# power.net
KiCad netlist of a schematic drawn in Altium Designer
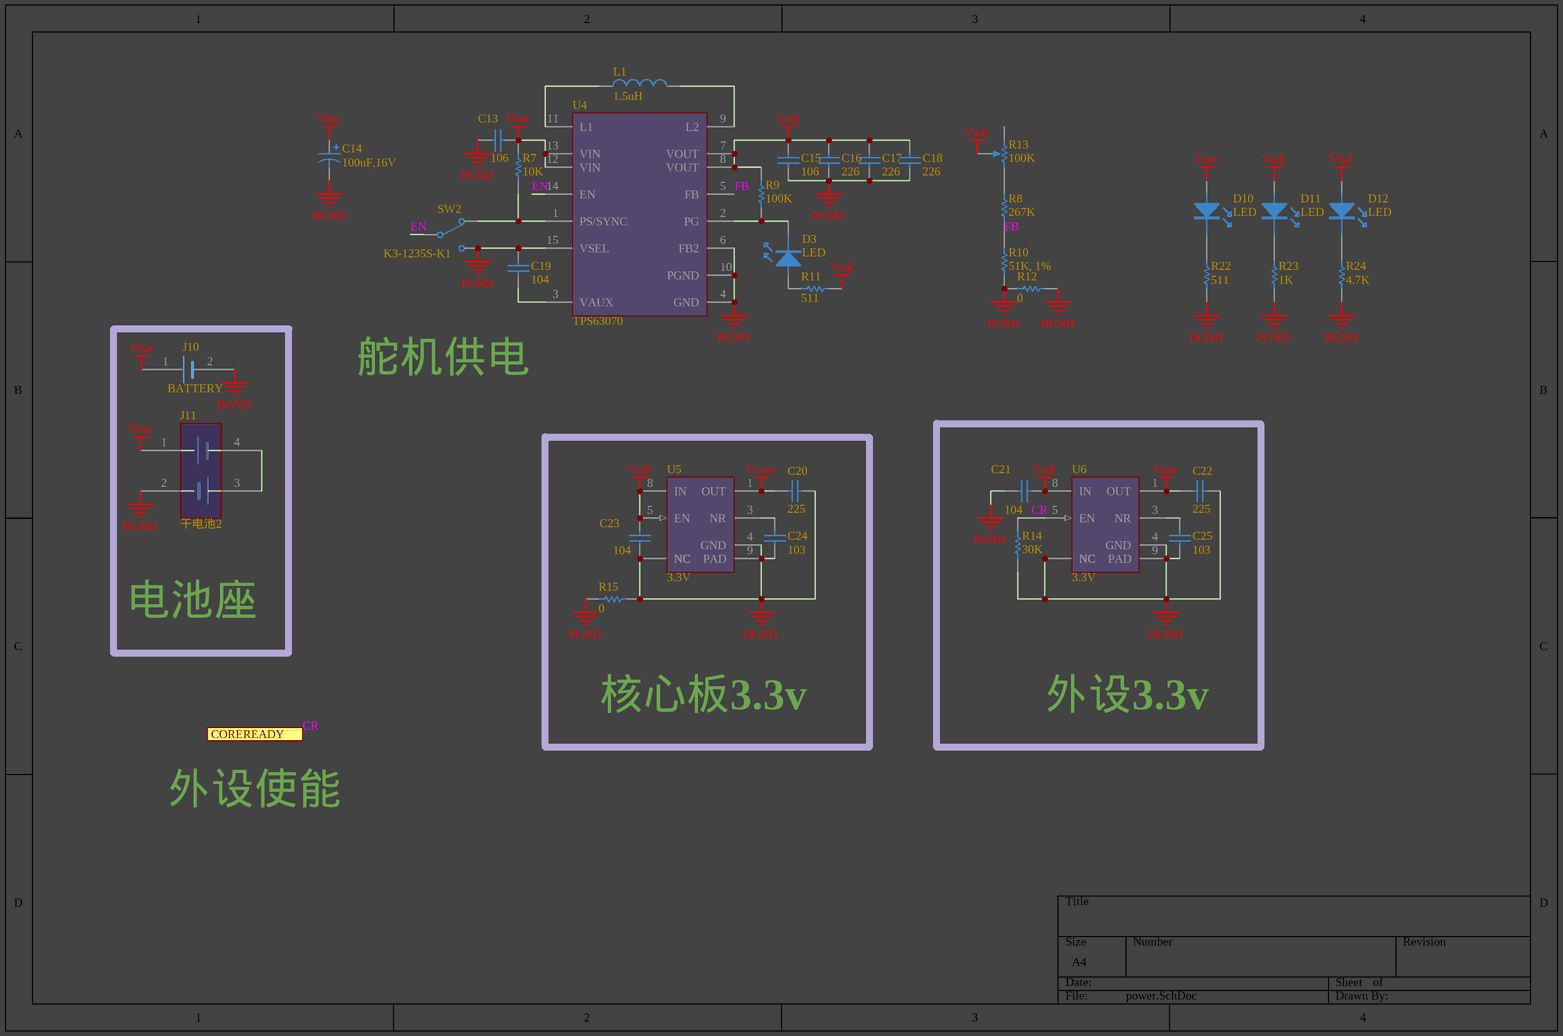
[diagram p0: power.SchDoc]

(export (version "E")
  (design (tool "Eeschema 10.0.6"))
  (components
    (comp (ref "C13")
      (value "106")
      (footprint "C0603")
      (description "Capacitor")
      (fields (field (name "PUBLISHER") "Altium Limited"))
      (libsource (lib "iMag") (part "电容"))
    )
    (comp (ref "C14")
      (value "100uF,16V")
      (footprint "贴片电解 6.3*5.4")
      (description "Polarized Capacitor (Axial)")
      (fields (field (name "PUBLISHER") "Altium Limited"))
      (libsource (lib "iMag") (part "电解电容"))
    )
    (comp (ref "C15")
      (value "106")
      (footprint "C0603")
      (description "Capacitor")
      (fields (field (name "PUBLISHER") "Altium Limited"))
      (libsource (lib "iMag") (part "电容"))
    )
    (comp (ref "C16")
      (value "226")
      (footprint "0805C")
      (description "Capacitor")
      (fields (field (name "PUBLISHER") "Altium Limited"))
      (libsource (lib "iMag") (part "电容"))
    )
    (comp (ref "C17")
      (value "226")
      (footprint "0805C")
      (description "Capacitor")
      (fields (field (name "PUBLISHER") "Altium Limited"))
      (libsource (lib "iMag") (part "电容"))
    )
    (comp (ref "C18")
      (value "226")
      (footprint "0805C")
      (description "Capacitor")
      (fields (field (name "PUBLISHER") "Altium Limited"))
      (libsource (lib "iMag") (part "电容"))
    )
    (comp (ref "C19")
      (value "104")
      (footprint "C0402")
      (description "Capacitor")
      (fields (field (name "PUBLISHER") "Altium Limited"))
      (libsource (lib "iMag") (part "电容"))
    )
    (comp (ref "C20")
      (value "225")
      (footprint "C0603")
      (description "X5R Capacitor")
      (fields (field (name "PUBLISHER") "Altium Limited"))
      (libsource (lib "iMag") (part "电容"))
    )
    (comp (ref "C21")
      (value "104")
      (footprint "C0402")
      (description "Capacitor")
      (fields (field (name "PUBLISHER") "Altium Limited"))
      (libsource (lib "iMag") (part "电容"))
    )
    (comp (ref "C22")
      (value "225")
      (footprint "C0603")
      (description "X5R Capacitor")
      (fields (field (name "PUBLISHER") "Altium Limited"))
      (libsource (lib "iMag") (part "电容"))
    )
    (comp (ref "C23")
      (value "104")
      (footprint "C0402")
      (description "Capacitor")
      (fields (field (name "PUBLISHER") "Altium Limited"))
      (libsource (lib "iMag") (part "电容"))
    )
    (comp (ref "C24")
      (value "103")
      (footprint "C0402")
      (description "Capacitor")
      (fields (field (name "PUBLISHER") "Altium Limited"))
      (libsource (lib "iMag") (part "电容"))
    )
    (comp (ref "C25")
      (value "103")
      (footprint "C0402")
      (description "Capacitor")
      (fields (field (name "PUBLISHER") "Altium Limited"))
      (libsource (lib "iMag") (part "电容"))
    )
    (comp (ref "D3") (value "LED") (footprint "LED 0603R") (libsource (lib "iMag") (part "LED")))
    (comp (ref "D10") (value "LED") (footprint "LED 0603Y") (libsource (lib "iMag") (part "LED")))
    (comp (ref "D11") (value "LED") (footprint "LED 0603G") (libsource (lib "iMag") (part "LED")))
    (comp (ref "D12") (value "LED") (footprint "LED 0603B") (libsource (lib "iMag") (part "LED")))
    (comp (ref "J10") (value "BATTERY") (footprint "T接头") (libsource (lib "iMag") (part "BATTERY")))
    (comp (ref "J11") (value "干电池2") (footprint "18650x2") (libsource (lib "iMag") (part "干电池2")))
    (comp (ref "L1")
      (value "1.5uH")
      (footprint "L5X5")
      (description "4.6A, 14.4mOhm")
      (libsource (lib "iMag") (part "贴片电感"))
    )
    (comp (ref "R7")
      (value "10K")
      (footprint "R0402")
      (description "Resistor")
      (fields (field (name "PUBLISHER") "Altium Limited"))
      (libsource (lib "iMag") (part "电阻"))
    )
    (comp (ref "R8")
      (value "267K")
      (footprint "R0402")
      (description "Resistor")
      (fields (field (name "PUBLISHER") "Altium Limited"))
      (libsource (lib "iMag") (part "电阻"))
    )
    (comp (ref "R9")
      (value "100K")
      (footprint "R0402")
      (description "Resistor")
      (fields (field (name "PUBLISHER") "Altium Limited"))
      (libsource (lib "iMag") (part "电阻"))
    )
    (comp (ref "R10")
      (value "51K, 1%")
      (footprint "R0402")
      (description "Resistor")
      (fields (field (name "PUBLISHER") "Altium Limited"))
      (libsource (lib "iMag") (part "电阻"))
    )
    (comp (ref "R11")
      (value "511")
      (footprint "R0402")
      (description "Resistor")
      (fields (field (name "PUBLISHER") "Altium Limited"))
      (libsource (lib "iMag") (part "电阻"))
    )
    (comp (ref "R12")
      (value "0")
      (footprint "R0603")
      (description "Resistor")
      (fields (field (name "PUBLISHER") "Altium Limited"))
      (libsource (lib "iMag") (part "电阻"))
    )
    (comp (ref "R13") (value "100K") (footprint "3296W") (libsource (lib "iMag") (part "电位器")))
    (comp (ref "R14")
      (value "30K")
      (footprint "R0402")
      (description "Resistor")
      (fields (field (name "PUBLISHER") "Altium Limited"))
      (libsource (lib "iMag") (part "电阻"))
    )
    (comp (ref "R15")
      (value "0")
      (footprint "R0603")
      (description "Resistor")
      (fields (field (name "PUBLISHER") "Altium Limited"))
      (libsource (lib "iMag") (part "电阻"))
    )
    (comp (ref "R22")
      (value "511")
      (footprint "R0402")
      (description "Resistor")
      (fields (field (name "PUBLISHER") "Altium Limited"))
      (libsource (lib "iMag") (part "电阻"))
    )
    (comp (ref "R23")
      (value "1K")
      (footprint "R0402")
      (description "Resistor")
      (fields (field (name "PUBLISHER") "Altium Limited"))
      (libsource (lib "iMag") (part "电阻"))
    )
    (comp (ref "R24")
      (value "4.7K")
      (footprint "R0402")
      (description "Resistor")
      (fields (field (name "PUBLISHER") "Altium Limited"))
      (libsource (lib "iMag") (part "电阻"))
    )
    (comp (ref "SW2")
      (value "K3-1235S-K1")
      (footprint "K3-1235S-K1")
      (description "Switch")
      (libsource (lib "iMag") (part "单刀双掷"))
    )
    (comp (ref "U4") (value "TPS63070") (footprint "VQFN-15") (libsource (lib "iMag") (part "TPS63070")))
    (comp (ref "U5")
      (value "3.3V")
      (footprint "VSON-8")
      (description "No Description Available")
      (fields
        (field (name "PARTNUMBER") "TPS73512DRBR")
        (field (name "ALTERNATE_PARTNUMBER") "TPS73512DRBT")
        (field (name "COPYRIGHT") "Copyright (C) 2018 Accelerated Designs. All rights reserved")
      )
      (libsource (lib "iMag") (part "TPS73512DRBR"))
    )
    (comp (ref "U6")
      (value "3.3V")
      (footprint "VSON-8")
      (description "No Description Available")
      (fields
        (field (name "PARTNUMBER") "TPS73512DRBR")
        (field (name "ALTERNATE_PARTNUMBER") "TPS73512DRBT")
        (field (name "COPYRIGHT") "Copyright (C) 2018 Accelerated Designs. All rights reserved")
      )
      (libsource (lib "iMag") (part "TPS73512DRBR"))
    )
  )
  (nets
    (net (code "1") (name "/CR") (class "Default")
      (node (ref "R14") (pin "1") (pinfunction "1_1") (pintype "passive"))
      (node (ref "U6") (pin "5") (pinfunction "EN_5") (pintype "input"))
    )
    (net (code "2") (name "/EN") (class "Default")
      (node (ref "SW2") (pin "2") (pinfunction "2_2") (pintype "passive"))
      (node (ref "U4") (pin "14") (pinfunction "EN_14") (pintype "passive"))
    )
    (net (code "3") (name "/FB") (class "Default")
      (node (ref "R10") (pin "1") (pinfunction "1_1") (pintype "passive"))
      (node (ref "R8") (pin "2") (pinfunction "2_2") (pintype "passive"))
      (node (ref "U4") (pin "5") (pinfunction "FB_5") (pintype "passive"))
    )
    (net (code "4") (name "BGND") (class "Default")
      (node (ref "C14") (pin "2") (pinfunction "2_2") (pintype "passive"))
      (node (ref "J10") (pin "2") (pinfunction "+_2") (pintype "passive"))
      (node (ref "J11") (pin "2") (pinfunction "+_2") (pintype "passive"))
      (node (ref "R12") (pin "1") (pinfunction "1_1") (pintype "passive"))
      (node (ref "R24") (pin "1") (pinfunction "1_1") (pintype "passive"))
    )
    (net (code "5") (name "DGND") (class "Default")
      (node (ref "C20") (pin "2") (pinfunction "2_2") (pintype "passive"))
      (node (ref "C22") (pin "2") (pinfunction "2_2") (pintype "passive"))
      (node (ref "C23") (pin "1") (pinfunction "1_1") (pintype "passive"))
      (node (ref "C24") (pin "1") (pinfunction "1_1") (pintype "passive"))
      (node (ref "C25") (pin "1") (pinfunction "1_1") (pintype "passive"))
      (node (ref "R14") (pin "2") (pinfunction "2_2") (pintype "passive"))
      (node (ref "R15") (pin "1") (pinfunction "1_1") (pintype "passive"))
      (node (ref "R22") (pin "1") (pinfunction "1_1") (pintype "passive"))
      (node (ref "U5") (pin "2") (pinfunction "NC_2") (pintype "passive"))
      (node (ref "U5") (pin "4") (pinfunction "GND_4") (pintype "power_in"))
      (node (ref "U5") (pin "6") (pinfunction "NC_6") (pintype "passive"))
      (node (ref "U5") (pin "7") (pinfunction "NC_7") (pintype "passive"))
      (node (ref "U5") (pin "9") (pinfunction "PAD_9") (pintype "power_in"))
      (node (ref "U6") (pin "2") (pinfunction "NC_2") (pintype "passive"))
      (node (ref "U6") (pin "4") (pinfunction "GND_4") (pintype "power_in"))
      (node (ref "U6") (pin "6") (pinfunction "NC_6") (pintype "passive"))
      (node (ref "U6") (pin "7") (pinfunction "NC_7") (pintype "passive"))
      (node (ref "U6") (pin "9") (pinfunction "PAD_9") (pintype "power_in"))
    )
    (net (code "6") (name "Net-(D3-1)") (class "Default")
      (node (ref "D3") (pin "A") (pinfunction "1_A") (pintype "passive"))
      (node (ref "R11") (pin "2") (pinfunction "2_2") (pintype "passive"))
    )
    (net (code "7") (name "Net-(D3-2)") (class "Default")
      (node (ref "D3") (pin "K") (pinfunction "2_K") (pintype "passive"))
      (node (ref "R9") (pin "1") (pinfunction "1_1") (pintype "passive"))
      (node (ref "U4") (pin "2") (pinfunction "PG_2") (pintype "passive"))
    )
    (net (code "8") (name "Net-(D10-2)") (class "Default")
      (node (ref "D10") (pin "K") (pinfunction "2_K") (pintype "passive"))
      (node (ref "R22") (pin "2") (pinfunction "2_2") (pintype "passive"))
    )
    (net (code "9") (name "Net-(D11-2)") (class "Default")
      (node (ref "D11") (pin "K") (pinfunction "2_K") (pintype "passive"))
      (node (ref "R23") (pin "2") (pinfunction "2_2") (pintype "passive"))
    )
    (net (code "10") (name "Net-(D12-2)") (class "Default")
      (node (ref "D12") (pin "K") (pinfunction "2_K") (pintype "passive"))
      (node (ref "R24") (pin "2") (pinfunction "2_2") (pintype "passive"))
    )
    (net (code "11") (name "Net-(J11-+-Pad3)") (class "Default")
      (node (ref "J11") (pin "3") (pinfunction "+_3") (pintype "passive"))
      (node (ref "J11") (pin "4") (pinfunction "+_4") (pintype "passive"))
    )
    (net (code "12") (name "Net-(R13-BOT)") (class "Default")
      (node (ref "R13") (pin "3") (pinfunction "BOT_3") (pintype "passive"))
      (node (ref "R8") (pin "1") (pinfunction "1_1") (pintype "passive"))
    )
    (net (code "13") (name "Net-(U4-L1)") (class "Default")
      (node (ref "L1") (pin "1") (pinfunction "1_1") (pintype "passive"))
      (node (ref "U4") (pin "11") (pinfunction "L1_11") (pintype "passive"))
    )
    (net (code "14") (name "Net-(U4-L2)") (class "Default")
      (node (ref "L1") (pin "2") (pinfunction "2_2") (pintype "passive"))
      (node (ref "U4") (pin "9") (pinfunction "L2_9") (pintype "passive"))
    )
    (net (code "15") (name "Net-(U4-PS{slash}SYNC)") (class "Default")
      (node (ref "R7") (pin "1") (pinfunction "1_1") (pintype "passive"))
      (node (ref "SW2") (pin "1") (pinfunction "1_1") (pintype "passive"))
      (node (ref "U4") (pin "1") (pinfunction "PS/SYNC_1") (pintype "passive"))
    )
    (net (code "16") (name "Net-(U4-VAUX)") (class "Default")
      (node (ref "C19") (pin "1") (pinfunction "1_1") (pintype "passive"))
      (node (ref "U4") (pin "3") (pinfunction "VAUX_3") (pintype "passive"))
    )
    (net (code "17") (name "Net-(U5-NR)") (class "Default")
      (node (ref "C24") (pin "2") (pinfunction "2_2") (pintype "passive"))
      (node (ref "U5") (pin "3") (pinfunction "NR_3") (pintype "passive"))
    )
    (net (code "18") (name "Net-(U6-NR)") (class "Default")
      (node (ref "C25") (pin "2") (pinfunction "2_2") (pintype "passive"))
      (node (ref "U6") (pin "3") (pinfunction "NR_3") (pintype "passive"))
    )
    (net (code "19") (name "PGND") (class "Default")
      (node (ref "C13") (pin "2") (pinfunction "2_2") (pintype "passive"))
      (node (ref "C15") (pin "1") (pinfunction "1_1") (pintype "passive"))
      (node (ref "C16") (pin "1") (pinfunction "1_1") (pintype "passive"))
      (node (ref "C17") (pin "1") (pinfunction "1_1") (pintype "passive"))
      (node (ref "C18") (pin "1") (pinfunction "1_1") (pintype "passive"))
      (node (ref "C19") (pin "2") (pinfunction "2_2") (pintype "passive"))
      (node (ref "C21") (pin "2") (pinfunction "2_2") (pintype "passive"))
      (node (ref "R10") (pin "2") (pinfunction "2_2") (pintype "passive"))
      (node (ref "R12") (pin "2") (pinfunction "2_2") (pintype "passive"))
      (node (ref "R15") (pin "2") (pinfunction "2_2") (pintype "passive"))
      (node (ref "R23") (pin "1") (pinfunction "1_1") (pintype "passive"))
      (node (ref "SW2") (pin "3") (pinfunction "3_3") (pintype "passive"))
      (node (ref "U4") (pin "10") (pinfunction "PGND_10") (pintype "passive"))
      (node (ref "U4") (pin "15") (pinfunction "VSEL_15") (pintype "passive"))
      (node (ref "U4") (pin "4") (pinfunction "GND_4") (pintype "passive"))
      (node (ref "U4") (pin "6") (pinfunction "FB2_6") (pintype "passive"))
    )
    (net (code "20") (name "Vadj") (class "Default")
      (node (ref "C15") (pin "2") (pinfunction "2_2") (pintype "passive"))
      (node (ref "C16") (pin "2") (pinfunction "2_2") (pintype "passive"))
      (node (ref "C17") (pin "2") (pinfunction "2_2") (pintype "passive"))
      (node (ref "C18") (pin "2") (pinfunction "2_2") (pintype "passive"))
      (node (ref "C21") (pin "1") (pinfunction "1_1") (pintype "passive"))
      (node (ref "C23") (pin "2") (pinfunction "2_2") (pintype "passive"))
      (node (ref "D11") (pin "A") (pinfunction "1_A") (pintype "passive"))
      (node (ref "R11") (pin "1") (pinfunction "1_1") (pintype "passive"))
      (node (ref "R13") (pin "2") (pinfunction "TAP_2") (pintype "passive"))
      (node (ref "R9") (pin "2") (pinfunction "2_2") (pintype "passive"))
      (node (ref "U4") (pin "7") (pinfunction "VOUT_7") (pintype "passive"))
      (node (ref "U4") (pin "8") (pinfunction "VOUT_8") (pintype "passive"))
      (node (ref "U5") (pin "5") (pinfunction "EN_5") (pintype "input"))
      (node (ref "U5") (pin "8") (pinfunction "IN_8") (pintype "power_in"))
      (node (ref "U6") (pin "8") (pinfunction "IN_8") (pintype "power_in"))
    )
    (net (code "21") (name "Vbat") (class "Default")
      (node (ref "C13") (pin "1") (pinfunction "1_1") (pintype "passive"))
      (node (ref "C14") (pin "1") (pinfunction "1_1") (pintype "passive"))
      (node (ref "D12") (pin "A") (pinfunction "1_A") (pintype "passive"))
      (node (ref "J10") (pin "1") (pinfunction "+_1") (pintype "passive"))
      (node (ref "J11") (pin "1") (pinfunction "+_1") (pintype "passive"))
      (node (ref "R7") (pin "2") (pinfunction "2_2") (pintype "passive"))
      (node (ref "U4") (pin "12") (pinfunction "VIN_12") (pintype "passive"))
      (node (ref "U4") (pin "13") (pinfunction "VIN_13") (pintype "passive"))
    )
    (net (code "22") (name "Vcore") (class "Default")
      (node (ref "C20") (pin "1") (pinfunction "1_1") (pintype "passive"))
      (node (ref "U5") (pin "1") (pinfunction "OUT_1") (pintype "power_in"))
    )
    (net (code "23") (name "Vper") (class "Default")
      (node (ref "C22") (pin "1") (pinfunction "1_1") (pintype "passive"))
      (node (ref "D10") (pin "A") (pinfunction "1_A") (pintype "passive"))
      (node (ref "U6") (pin "1") (pinfunction "OUT_1") (pintype "power_in"))
    )
    (net (code "24") (name "unconnected-(R13-TOP-Pad1)") (class "Default")
      (node (ref "R13") (pin "1") (pinfunction "TOP_1") (pintype "passive"))
    )
  )
)
